# Ethernet_Con.net
KiCad netlist of a schematic drawn in Altium Designer
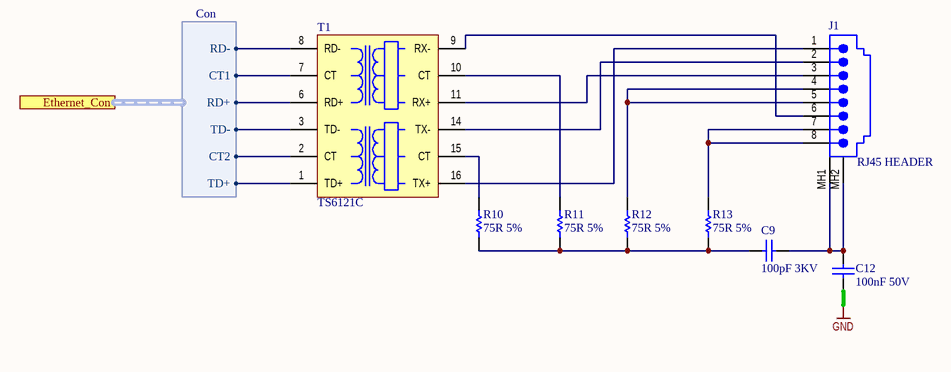
[diagram p0: Ethernet_Con.SchDoc]

(export (version "E")
  (design (tool "Eeschema 10.0.6"))
  (components
    (comp (ref "C9")
      (value "100pF 3KV")
      (footprint "CAPR7_5-3_6x7_5")
      (description "Capacitor")
      (libsource (lib "PHY") (part "CAP-NP"))
    )
    (comp (ref "C12")
      (value "100nF 50V")
      (footprint "CAPC2012")
      (description "Capacitor")
      (libsource (lib "PHY") (part "CAP-NP"))
    )
    (comp (ref "J1")
      (value "RJ45 HEADER")
      (footprint "95122-2881")
      (description "Right Angle, Standard Profile, External Shield PCB Jack")
      (libsource (lib "PHY") (part "CON-RJ45-10-RA"))
    )
    (comp (ref "R10")
      (value "75R 5%")
      (footprint "RESC2012")
      (description "Resistor")
      (libsource (lib "PHY") (part "RES"))
    )
    (comp (ref "R11")
      (value "75R 5%")
      (footprint "RESC2012")
      (description "Resistor")
      (libsource (lib "PHY") (part "RES"))
    )
    (comp (ref "R12")
      (value "75R 5%")
      (footprint "RESC2012")
      (description "Resistor")
      (libsource (lib "PHY") (part "RES"))
    )
    (comp (ref "R13")
      (value "75R 5%")
      (footprint "RESC2012")
      (description "Resistor")
      (libsource (lib "PHY") (part "RES"))
    )
    (comp (ref "T1")
      (value "TS6121C")
      (footprint "SOIC127P910-16")
      (description "Bothhand 10/100 BaseT Pulse Transformer")
      (libsource (lib "PHY") (part "TS6121C"))
    )
  )
  (nets
    (net (code "2") (name "/CT1") (class "Default")
      (node (ref "T1") (pin "7") (pinfunction "CT_7") (pintype "passive"))
    )
    (net (code "3") (name "/CT2") (class "Default")
      (node (ref "T1") (pin "2") (pinfunction "CT_2") (pintype "passive"))
    )
    (net (code "4") (name "/RD+") (class "Default")
      (node (ref "T1") (pin "6") (pinfunction "RD+_6") (pintype "passive"))
    )
    (net (code "5") (name "/RD-") (class "Default")
      (node (ref "T1") (pin "8") (pinfunction "RD-_8") (pintype "passive"))
    )
    (net (code "6") (name "/TD+") (class "Default")
      (node (ref "T1") (pin "1") (pinfunction "TD+_1") (pintype "passive"))
    )
    (net (code "7") (name "/TD-") (class "Default")
      (node (ref "T1") (pin "3") (pinfunction "TD-_3") (pintype "passive"))
    )
    (net (code "9") (name "GND") (class "Default")
      (node (ref "C12") (pin "1") (pinfunction "1_1") (pintype "passive"))
    )
    (net (code "10") (name "Net-(C9-Pad1)") (class "Default")
      (node (ref "C9") (pin "1") (pinfunction "1_1") (pintype "passive"))
      (node (ref "R10") (pin "2") (pinfunction "2_2") (pintype "passive"))
      (node (ref "R11") (pin "2") (pinfunction "2_2") (pintype "passive"))
      (node (ref "R12") (pin "2") (pinfunction "2_2") (pintype "passive"))
      (node (ref "R13") (pin "2") (pinfunction "2_2") (pintype "passive"))
    )
    (net (code "11") (name "Net-(C12-Pad2)") (class "Default")
      (node (ref "C12") (pin "2") (pinfunction "2_2") (pintype "passive"))
      (node (ref "C9") (pin "2") (pinfunction "2_2") (pintype "passive"))
      (node (ref "J1") (pin "MH1") (pinfunction "Shield_MH1") (pintype "passive"))
      (node (ref "J1") (pin "MH2") (pinfunction "Shield_MH2") (pintype "passive"))
    )
    (net (code "12") (name "Net-(J1-Pad4)") (class "Default")
      (node (ref "J1") (pin "4") (pinfunction "4_4") (pintype "passive"))
      (node (ref "J1") (pin "5") (pinfunction "5_5") (pintype "passive"))
      (node (ref "R12") (pin "1") (pinfunction "1_1") (pintype "passive"))
    )
    (net (code "13") (name "Net-(J1-Pad7)") (class "Default")
      (node (ref "J1") (pin "7") (pinfunction "7_7") (pintype "passive"))
      (node (ref "J1") (pin "8") (pinfunction "8_8") (pintype "passive"))
      (node (ref "R13") (pin "1") (pinfunction "1_1") (pintype "passive"))
    )
    (net (code "14") (name "Net-(R10-Pad1)") (class "Default")
      (node (ref "R10") (pin "1") (pinfunction "1_1") (pintype "passive"))
      (node (ref "T1") (pin "15") (pinfunction "CT_15") (pintype "passive"))
    )
    (net (code "15") (name "Net-(R11-Pad1)") (class "Default")
      (node (ref "R11") (pin "1") (pinfunction "1_1") (pintype "passive"))
      (node (ref "T1") (pin "10") (pinfunction "CT_10") (pintype "passive"))
    )
    (net (code "16") (name "Net-(T1-RX+)") (class "Default")
      (node (ref "J1") (pin "3") (pinfunction "3_3") (pintype "passive"))
      (node (ref "T1") (pin "11") (pinfunction "RX+_11") (pintype "passive"))
    )
    (net (code "17") (name "Net-(T1-RX-)") (class "Default")
      (node (ref "J1") (pin "6") (pinfunction "6_6") (pintype "passive"))
      (node (ref "T1") (pin "9") (pinfunction "RX-_9") (pintype "passive"))
    )
    (net (code "18") (name "Net-(T1-TX+)") (class "Default")
      (node (ref "J1") (pin "1") (pinfunction "1_1") (pintype "passive"))
      (node (ref "T1") (pin "16") (pinfunction "TX+_16") (pintype "passive"))
    )
    (net (code "19") (name "Net-(T1-TX-)") (class "Default")
      (node (ref "J1") (pin "2") (pinfunction "2_2") (pintype "passive"))
      (node (ref "T1") (pin "14") (pinfunction "TX-_14") (pintype "passive"))
    )
  )
)
